# 5_SDRAM.net
KiCad netlist of a schematic drawn in Altium Designer
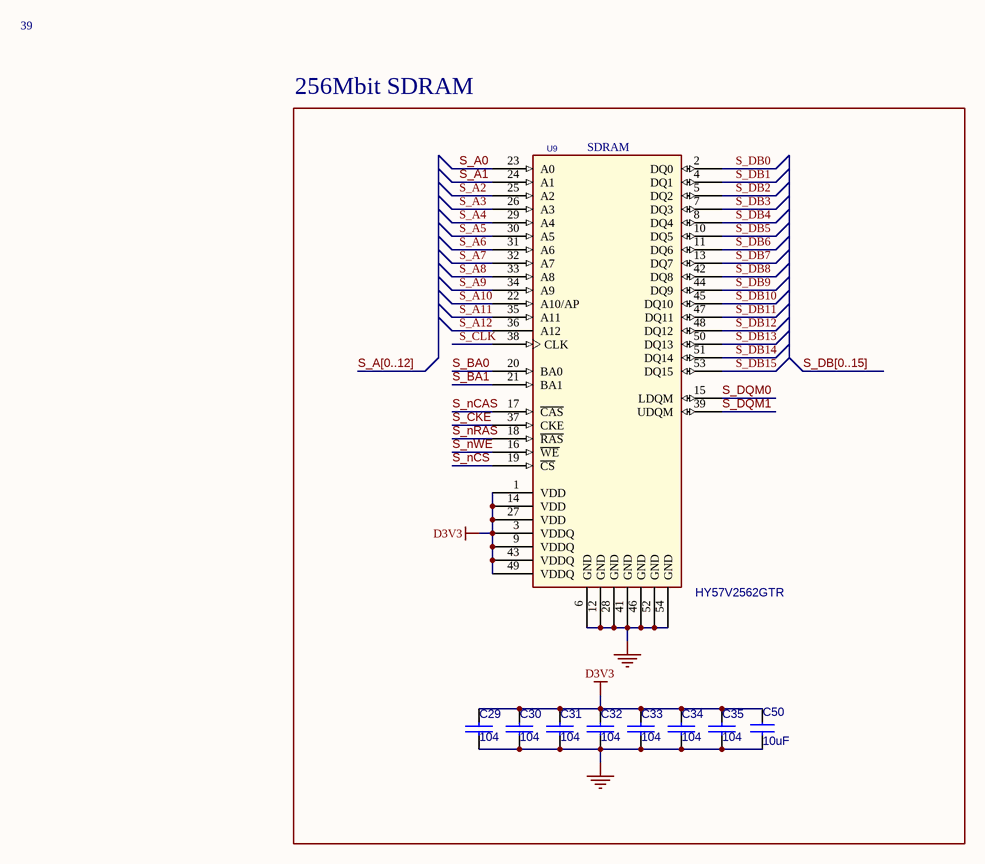
[diagram p0: 5_SDRAM.SchDoc]

(export (version "E")
  (design (tool "Eeschema 10.0.6"))
  (components
    (comp (ref "C29") (value "104") (libsource (lib "*") (part "C_Dup2")))
    (comp (ref "C30") (value "104") (libsource (lib "*") (part "C_Dup2")))
    (comp (ref "C31") (value "104") (libsource (lib "*") (part "C_Dup2")))
    (comp (ref "C32") (value "104") (libsource (lib "*") (part "C_Dup2")))
    (comp (ref "C33") (value "104") (libsource (lib "*") (part "C_Dup2")))
    (comp (ref "C34") (value "104") (libsource (lib "*") (part "C_Dup2")))
    (comp (ref "C35") (value "104") (libsource (lib "*") (part "C_Dup2")))
    (comp (ref "C50") (value "10uF") (libsource (lib "*") (part "CAP NP_Dup2")))
    (comp (ref "U9") (value "HY57V2562GTR") (libsource (lib "*") (part "HY57651620/SO_0")))
  )
  (nets
    (net (code "1") (name "/S_A0") (class "Default")
      (node (ref "U9") (pin "23") (pinfunction "A0_23") (pintype "input"))
    )
    (net (code "2") (name "/S_A1") (class "Default")
      (node (ref "U9") (pin "24") (pinfunction "A1_24") (pintype "input"))
    )
    (net (code "3") (name "/S_A2") (class "Default")
      (node (ref "U9") (pin "25") (pinfunction "A2_25") (pintype "input"))
    )
    (net (code "4") (name "/S_A3") (class "Default")
      (node (ref "U9") (pin "26") (pinfunction "A3_26") (pintype "input"))
    )
    (net (code "5") (name "/S_A4") (class "Default")
      (node (ref "U9") (pin "29") (pinfunction "A4_29") (pintype "input"))
    )
    (net (code "6") (name "/S_A5") (class "Default")
      (node (ref "U9") (pin "30") (pinfunction "A5_30") (pintype "input"))
    )
    (net (code "7") (name "/S_A6") (class "Default")
      (node (ref "U9") (pin "31") (pinfunction "A6_31") (pintype "input"))
    )
    (net (code "8") (name "/S_A7") (class "Default")
      (node (ref "U9") (pin "32") (pinfunction "A7_32") (pintype "input"))
    )
    (net (code "9") (name "/S_A8") (class "Default")
      (node (ref "U9") (pin "33") (pinfunction "A8_33") (pintype "input"))
    )
    (net (code "10") (name "/S_A9") (class "Default")
      (node (ref "U9") (pin "34") (pinfunction "A9_34") (pintype "input"))
    )
    (net (code "11") (name "/S_A10") (class "Default")
      (node (ref "U9") (pin "22") (pinfunction "A10/AP_22") (pintype "input"))
    )
    (net (code "12") (name "/S_A11") (class "Default")
      (node (ref "U9") (pin "35") (pinfunction "A11_35") (pintype "input"))
    )
    (net (code "13") (name "/S_A12") (class "Default")
      (node (ref "U9") (pin "36") (pinfunction "A12_36") (pintype "passive"))
    )
    (net (code "15") (name "/S_BA0") (class "Default")
      (node (ref "U9") (pin "20") (pinfunction "BA0_20") (pintype "input"))
    )
    (net (code "16") (name "/S_BA1") (class "Default")
      (node (ref "U9") (pin "21") (pinfunction "BA1_21") (pintype "input"))
    )
    (net (code "17") (name "/S_CKE") (class "Default")
      (node (ref "U9") (pin "37") (pinfunction "CKE_37") (pintype "input"))
    )
    (net (code "18") (name "/S_CLK") (class "Default")
      (node (ref "U9") (pin "38") (pinfunction "CLK_38") (pintype "input"))
    )
    (net (code "19") (name "/S_DB0") (class "Default")
      (node (ref "U9") (pin "2") (pinfunction "DQ0_2") (pintype "bidirectional"))
    )
    (net (code "20") (name "/S_DB1") (class "Default")
      (node (ref "U9") (pin "4") (pinfunction "DQ1_4") (pintype "bidirectional"))
    )
    (net (code "21") (name "/S_DB2") (class "Default")
      (node (ref "U9") (pin "5") (pinfunction "DQ2_5") (pintype "bidirectional"))
    )
    (net (code "22") (name "/S_DB3") (class "Default")
      (node (ref "U9") (pin "7") (pinfunction "DQ3_7") (pintype "bidirectional"))
    )
    (net (code "23") (name "/S_DB4") (class "Default")
      (node (ref "U9") (pin "8") (pinfunction "DQ4_8") (pintype "bidirectional"))
    )
    (net (code "24") (name "/S_DB5") (class "Default")
      (node (ref "U9") (pin "10") (pinfunction "DQ5_10") (pintype "bidirectional"))
    )
    (net (code "25") (name "/S_DB6") (class "Default")
      (node (ref "U9") (pin "11") (pinfunction "DQ6_11") (pintype "bidirectional"))
    )
    (net (code "26") (name "/S_DB7") (class "Default")
      (node (ref "U9") (pin "13") (pinfunction "DQ7_13") (pintype "bidirectional"))
    )
    (net (code "27") (name "/S_DB8") (class "Default")
      (node (ref "U9") (pin "42") (pinfunction "DQ8_42") (pintype "bidirectional"))
    )
    (net (code "28") (name "/S_DB9") (class "Default")
      (node (ref "U9") (pin "44") (pinfunction "DQ9_44") (pintype "bidirectional"))
    )
    (net (code "29") (name "/S_DB10") (class "Default")
      (node (ref "U9") (pin "45") (pinfunction "DQ10_45") (pintype "bidirectional"))
    )
    (net (code "30") (name "/S_DB11") (class "Default")
      (node (ref "U9") (pin "47") (pinfunction "DQ11_47") (pintype "bidirectional"))
    )
    (net (code "31") (name "/S_DB12") (class "Default")
      (node (ref "U9") (pin "48") (pinfunction "DQ12_48") (pintype "bidirectional"))
    )
    (net (code "32") (name "/S_DB13") (class "Default")
      (node (ref "U9") (pin "50") (pinfunction "DQ13_50") (pintype "bidirectional"))
    )
    (net (code "33") (name "/S_DB14") (class "Default")
      (node (ref "U9") (pin "51") (pinfunction "DQ14_51") (pintype "bidirectional"))
    )
    (net (code "34") (name "/S_DB15") (class "Default")
      (node (ref "U9") (pin "53") (pinfunction "DQ15_53") (pintype "bidirectional"))
    )
    (net (code "36") (name "/S_DQM0") (class "Default")
      (node (ref "U9") (pin "15") (pinfunction "LDQM_15") (pintype "bidirectional"))
    )
    (net (code "37") (name "/S_DQM1") (class "Default")
      (node (ref "U9") (pin "39") (pinfunction "UDQM_39") (pintype "bidirectional"))
    )
    (net (code "38") (name "/S_nCAS") (class "Default")
      (node (ref "U9") (pin "17") (pinfunction "~{CAS}_17") (pintype "input"))
    )
    (net (code "39") (name "/S_nCS") (class "Default")
      (node (ref "U9") (pin "19") (pinfunction "~{CS}_19") (pintype "input"))
    )
    (net (code "40") (name "/S_nRAS") (class "Default")
      (node (ref "U9") (pin "18") (pinfunction "~{RAS}_18") (pintype "input"))
    )
    (net (code "41") (name "/S_nWE") (class "Default")
      (node (ref "U9") (pin "16") (pinfunction "~{WE}_16") (pintype "input"))
    )
    (net (code "42") (name "D3V3") (class "Default")
      (node (ref "C29") (pin "1") (pinfunction "1_1") (pintype "passive"))
      (node (ref "C30") (pin "1") (pinfunction "1_1") (pintype "passive"))
      (node (ref "C31") (pin "1") (pinfunction "1_1") (pintype "passive"))
      (node (ref "C32") (pin "1") (pinfunction "1_1") (pintype "passive"))
      (node (ref "C33") (pin "1") (pinfunction "1_1") (pintype "passive"))
      (node (ref "C34") (pin "1") (pinfunction "1_1") (pintype "passive"))
      (node (ref "C35") (pin "1") (pinfunction "1_1") (pintype "passive"))
      (node (ref "C50") (pin "1") (pinfunction "1_1") (pintype "passive"))
      (node (ref "U9") (pin "1") (pinfunction "VDD_1") (pintype "power_in"))
      (node (ref "U9") (pin "14") (pinfunction "VDD_14") (pintype "power_in"))
      (node (ref "U9") (pin "27") (pinfunction "VDD_27") (pintype "power_in"))
      (node (ref "U9") (pin "3") (pinfunction "VDDQ_3") (pintype "power_in"))
      (node (ref "U9") (pin "43") (pinfunction "VDDQ_43") (pintype "power_in"))
      (node (ref "U9") (pin "49") (pinfunction "VDDQ_49") (pintype "power_in"))
      (node (ref "U9") (pin "9") (pinfunction "VDDQ_9") (pintype "power_in"))
    )
    (net (code "43") (name "GND") (class "Default")
      (node (ref "C29") (pin "2") (pinfunction "2_2") (pintype "passive"))
      (node (ref "C30") (pin "2") (pinfunction "2_2") (pintype "passive"))
      (node (ref "C31") (pin "2") (pinfunction "2_2") (pintype "passive"))
      (node (ref "C32") (pin "2") (pinfunction "2_2") (pintype "passive"))
      (node (ref "C33") (pin "2") (pinfunction "2_2") (pintype "passive"))
      (node (ref "C34") (pin "2") (pinfunction "2_2") (pintype "passive"))
      (node (ref "C35") (pin "2") (pinfunction "2_2") (pintype "passive"))
      (node (ref "C50") (pin "2") (pinfunction "2_2") (pintype "passive"))
      (node (ref "U9") (pin "12") (pinfunction "GND_12") (pintype "power_in"))
      (node (ref "U9") (pin "28") (pinfunction "GND_28") (pintype "power_in"))
      (node (ref "U9") (pin "41") (pinfunction "GND_41") (pintype "power_in"))
      (node (ref "U9") (pin "46") (pinfunction "GND_46") (pintype "power_in"))
      (node (ref "U9") (pin "52") (pinfunction "GND_52") (pintype "power_in"))
      (node (ref "U9") (pin "54") (pinfunction "GND_54") (pintype "power_in"))
      (node (ref "U9") (pin "6") (pinfunction "GND_6") (pintype "power_in"))
    )
  )
)
